# ads1115_shiled.net
KiCad netlist of a schematic drawn in EAGLE
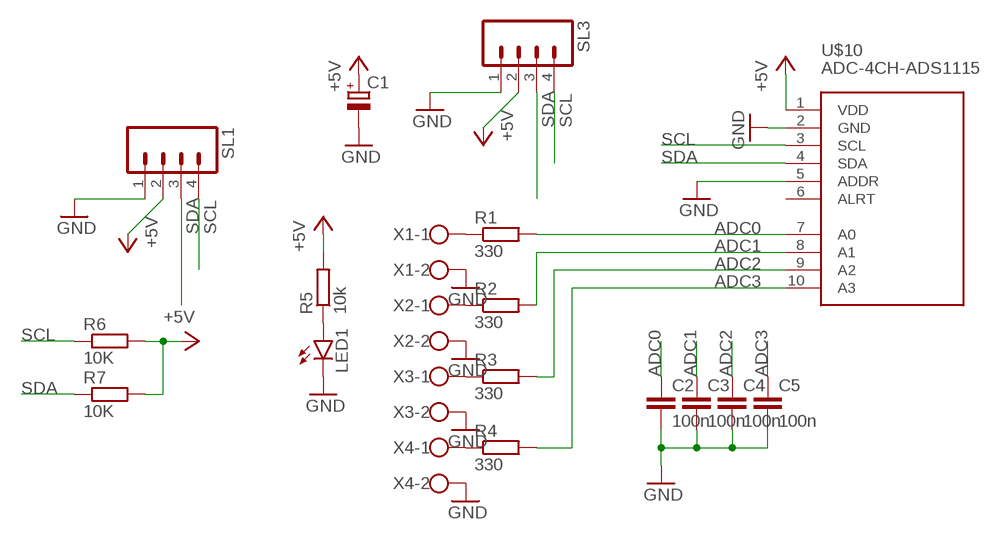
[diagram p0: schematic, sheet 1]

(export (version "E")
  (design (tool "Eeschema 10.0.6"))
  (components
    (comp (ref "C1")
      (value "CPOL-EUE5-8.5")
      (footprint "eagle-import:E5-8,5")
      (libsource (lib "eagle-import") (part "CPOL-EUE5-8.5"))
    )
    (comp (ref "C2")
      (value "100n")
      (footprint "eagle-import:C1206")
      (libsource (lib "eagle-import") (part "C-EUC1206"))
    )
    (comp (ref "C3")
      (value "100n")
      (footprint "eagle-import:C1206")
      (libsource (lib "eagle-import") (part "C-EUC1206"))
    )
    (comp (ref "C4")
      (value "100n")
      (footprint "eagle-import:C1206")
      (libsource (lib "eagle-import") (part "C-EUC1206"))
    )
    (comp (ref "C5")
      (value "100n")
      (footprint "eagle-import:C1206")
      (libsource (lib "eagle-import") (part "C-EUC1206"))
    )
    (comp (ref "LED1")
      (value "LED3MM")
      (footprint "eagle-import:LED3MM")
      (libsource (lib "eagle-import") (part "LED3MM"))
    )
    (comp (ref "R1")
      (value "330")
      (footprint "eagle-import:M1206")
      (libsource (lib "eagle-import") (part "R-EU_M1206"))
    )
    (comp (ref "R2")
      (value "330")
      (footprint "eagle-import:M1206")
      (libsource (lib "eagle-import") (part "R-EU_M1206"))
    )
    (comp (ref "R3")
      (value "330")
      (footprint "eagle-import:M1206")
      (libsource (lib "eagle-import") (part "R-EU_M1206"))
    )
    (comp (ref "R4")
      (value "330")
      (footprint "eagle-import:M1206")
      (libsource (lib "eagle-import") (part "R-EU_M1206"))
    )
    (comp (ref "R5")
      (value "10k")
      (footprint "eagle-import:M1206")
      (libsource (lib "eagle-import") (part "R-EU_M1206"))
    )
    (comp (ref "R6")
      (value "10K")
      (footprint "eagle-import:M1206")
      (libsource (lib "eagle-import") (part "R-EU_M1206"))
    )
    (comp (ref "R7")
      (value "10K")
      (footprint "eagle-import:M1206")
      (libsource (lib "eagle-import") (part "R-EU_M1206"))
    )
    (comp (ref "SL1")
      (value "M04")
      (footprint "eagle-import:04P")
      (libsource (lib "eagle-import") (part "M04"))
    )
    (comp (ref "SL3")
      (value "M04")
      (footprint "eagle-import:04P")
      (libsource (lib "eagle-import") (part "M04"))
    )
    (comp (ref "U$10")
      (value "ADC-4CH-ADS1115")
      (footprint "eagle-import:ADC-4CH-ADS1115")
      (libsource (lib "eagle-import") (part "ADC-4CH-ADS1115"))
    )
    (comp (ref "X1")
      (value "W237-102")
      (footprint "eagle-import:W237-102")
      (fields (field (name "MPN") "237-102"))
      (libsource (lib "eagle-import") (part "W237-102"))
    )
    (comp (ref "X2")
      (value "W237-102")
      (footprint "eagle-import:W237-102")
      (fields (field (name "MPN") "237-102"))
      (libsource (lib "eagle-import") (part "W237-102"))
    )
    (comp (ref "X3")
      (value "W237-102")
      (footprint "eagle-import:W237-102")
      (fields (field (name "MPN") "237-102"))
      (libsource (lib "eagle-import") (part "W237-102"))
    )
    (comp (ref "X4")
      (value "W237-102")
      (footprint "eagle-import:W237-102")
      (fields (field (name "MPN") "237-102"))
      (libsource (lib "eagle-import") (part "W237-102"))
    )
  )
  (nets
    (net (code "1") (name "+5V") (class "Default")
      (node (ref "C1") (pin "+") (pinfunction "+_+") (pintype "passive"))
      (node (ref "R5") (pin "2") (pinfunction "2_2") (pintype "passive"))
      (node (ref "R6") (pin "2") (pinfunction "2_2") (pintype "passive"))
      (node (ref "R7") (pin "2") (pinfunction "2_2") (pintype "passive"))
      (node (ref "SL1") (pin "2") (pinfunction "2_2") (pintype "passive"))
      (node (ref "SL3") (pin "2") (pinfunction "2_2") (pintype "passive"))
      (node (ref "U$10") (pin "1") (pinfunction "VDD_1") (pintype "power_in"))
    )
    (net (code "2") (name "/ADC0") (class "Default")
      (node (ref "C2") (pin "1") (pinfunction "1_1") (pintype "passive"))
      (node (ref "R1") (pin "2") (pinfunction "2_2") (pintype "passive"))
      (node (ref "U$10") (pin "7") (pinfunction "A0_7") (pintype "input"))
    )
    (net (code "3") (name "/ADC1") (class "Default")
      (node (ref "C3") (pin "1") (pinfunction "1_1") (pintype "passive"))
      (node (ref "R2") (pin "2") (pinfunction "2_2") (pintype "passive"))
      (node (ref "U$10") (pin "8") (pinfunction "A1_8") (pintype "input"))
    )
    (net (code "4") (name "/ADC2") (class "Default")
      (node (ref "C4") (pin "1") (pinfunction "1_1") (pintype "passive"))
      (node (ref "R3") (pin "2") (pinfunction "2_2") (pintype "passive"))
      (node (ref "U$10") (pin "9") (pinfunction "A2_9") (pintype "input"))
    )
    (net (code "5") (name "/ADC3") (class "Default")
      (node (ref "C5") (pin "1") (pinfunction "1_1") (pintype "passive"))
      (node (ref "R4") (pin "2") (pinfunction "2_2") (pintype "passive"))
      (node (ref "U$10") (pin "10") (pinfunction "A3_10") (pintype "input"))
    )
    (net (code "6") (name "/SCL") (class "Default")
      (node (ref "R6") (pin "1") (pinfunction "1_1") (pintype "passive"))
      (node (ref "SL1") (pin "4") (pinfunction "4_4") (pintype "passive"))
      (node (ref "SL3") (pin "4") (pinfunction "4_4") (pintype "passive"))
      (node (ref "U$10") (pin "3") (pinfunction "SCL_3") (pintype "bidirectional"))
    )
    (net (code "7") (name "/SDA") (class "Default")
      (node (ref "R7") (pin "1") (pinfunction "1_1") (pintype "passive"))
      (node (ref "SL1") (pin "3") (pinfunction "3_3") (pintype "passive"))
      (node (ref "SL3") (pin "3") (pinfunction "3_3") (pintype "passive"))
      (node (ref "U$10") (pin "4") (pinfunction "SDA_4") (pintype "bidirectional"))
    )
    (net (code "8") (name "GND") (class "Default")
      (node (ref "C1") (pin "-") (pinfunction "-_-") (pintype "passive"))
      (node (ref "C2") (pin "2") (pinfunction "2_2") (pintype "passive"))
      (node (ref "C3") (pin "2") (pinfunction "2_2") (pintype "passive"))
      (node (ref "C4") (pin "2") (pinfunction "2_2") (pintype "passive"))
      (node (ref "C5") (pin "2") (pinfunction "2_2") (pintype "passive"))
      (node (ref "LED1") (pin "K") (pinfunction "C_K") (pintype "passive"))
      (node (ref "SL1") (pin "1") (pinfunction "1_1") (pintype "passive"))
      (node (ref "SL3") (pin "1") (pinfunction "1_1") (pintype "passive"))
      (node (ref "U$10") (pin "2") (pinfunction "GND_2") (pintype "power_in"))
      (node (ref "U$10") (pin "5") (pinfunction "ADDR_5") (pintype "bidirectional"))
      (node (ref "X1") (pin "2") (pinfunction "KL_2") (pintype "passive"))
      (node (ref "X2") (pin "2") (pinfunction "KL_2") (pintype "passive"))
      (node (ref "X3") (pin "2") (pinfunction "KL_2") (pintype "passive"))
      (node (ref "X4") (pin "2") (pinfunction "KL_2") (pintype "passive"))
    )
    (net (code "9") (name "Net-(LED1-PadA)") (class "Default")
      (node (ref "LED1") (pin "A") (pinfunction "A_A") (pintype "passive"))
      (node (ref "R5") (pin "1") (pinfunction "1_1") (pintype "passive"))
    )
    (net (code "10") (name "Net-(X1A-KL)") (class "Default")
      (node (ref "R1") (pin "1") (pinfunction "1_1") (pintype "passive"))
      (node (ref "X1") (pin "1") (pinfunction "KL_1") (pintype "passive"))
    )
    (net (code "11") (name "Net-(X2A-KL)") (class "Default")
      (node (ref "R2") (pin "1") (pinfunction "1_1") (pintype "passive"))
      (node (ref "X2") (pin "1") (pinfunction "KL_1") (pintype "passive"))
    )
    (net (code "12") (name "Net-(X3A-KL)") (class "Default")
      (node (ref "R3") (pin "1") (pinfunction "1_1") (pintype "passive"))
      (node (ref "X3") (pin "1") (pinfunction "KL_1") (pintype "passive"))
    )
    (net (code "13") (name "Net-(X4A-KL)") (class "Default")
      (node (ref "R4") (pin "1") (pinfunction "1_1") (pintype "passive"))
      (node (ref "X4") (pin "1") (pinfunction "KL_1") (pintype "passive"))
    )
    (net (code "14") (name "unconnected-(U$10-ALRT-Pad6)") (class "Default")
      (node (ref "U$10") (pin "6") (pinfunction "ALRT_6") (pintype "bidirectional"))
    )
  )
)
